# n64cart-v3-soic-16-usbc.net
KiCad netlist of a schematic drawn in EAGLE
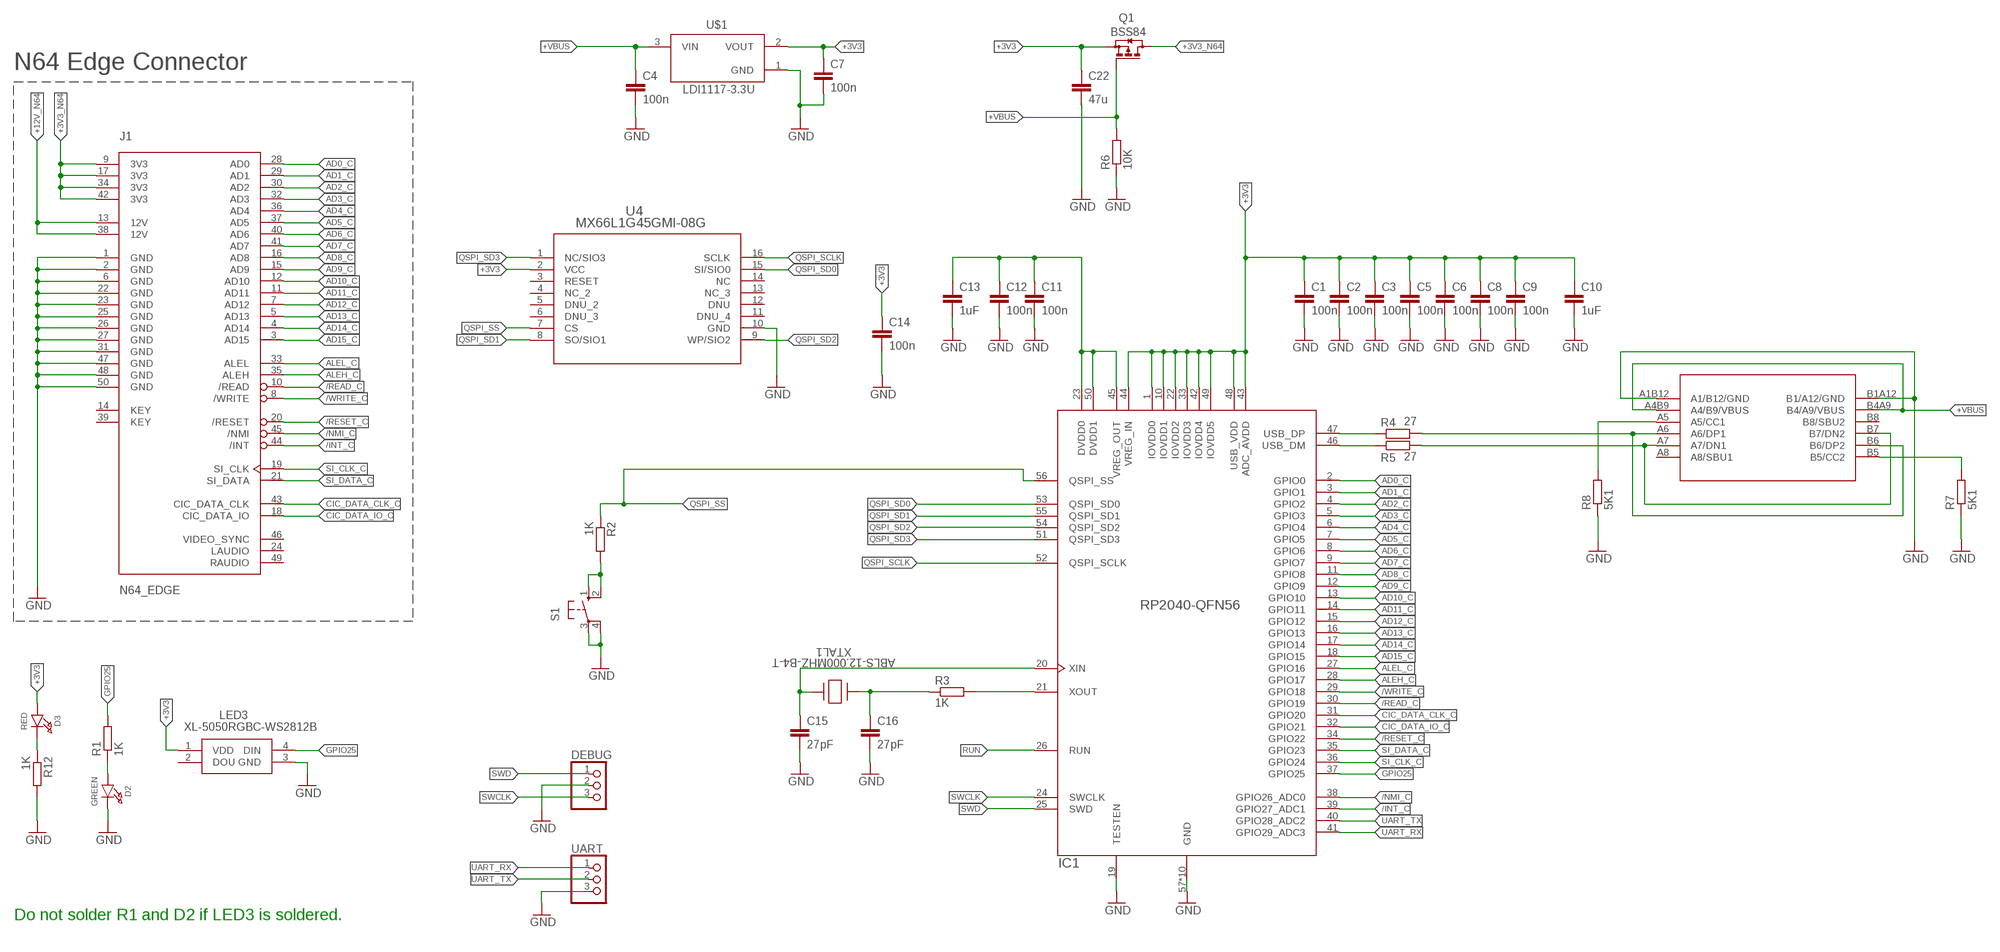
[diagram p0: schematic, sheet 1]

(export (version "E")
  (design (tool "Eeschema 10.0.6"))
  (components
    (comp (ref "C1")
      (value "100n")
      (footprint "eagle-import:C0402")
      (libsource (lib "eagle-import") (part "C-EUC0402"))
    )
    (comp (ref "C2")
      (value "100n")
      (footprint "eagle-import:C0402")
      (libsource (lib "eagle-import") (part "C-EUC0402"))
    )
    (comp (ref "C3")
      (value "100n")
      (footprint "eagle-import:C0402")
      (libsource (lib "eagle-import") (part "C-EUC0402"))
    )
    (comp (ref "C4")
      (value "100n")
      (footprint "eagle-import:C0603")
      (libsource (lib "eagle-import") (part "C-EUC0603"))
    )
    (comp (ref "C5")
      (value "100n")
      (footprint "eagle-import:C0402")
      (libsource (lib "eagle-import") (part "C-EUC0402"))
    )
    (comp (ref "C6")
      (value "100n")
      (footprint "eagle-import:C0402")
      (libsource (lib "eagle-import") (part "C-EUC0402"))
    )
    (comp (ref "C7")
      (value "100n")
      (footprint "eagle-import:C0603")
      (libsource (lib "eagle-import") (part "C-EUC0603"))
    )
    (comp (ref "C8")
      (value "100n")
      (footprint "eagle-import:C0402")
      (libsource (lib "eagle-import") (part "C-EUC0402"))
    )
    (comp (ref "C9")
      (value "100n")
      (footprint "eagle-import:C0402")
      (libsource (lib "eagle-import") (part "C-EUC0402"))
    )
    (comp (ref "C10")
      (value "1uF")
      (footprint "eagle-import:C0402")
      (libsource (lib "eagle-import") (part "C-EUC0402"))
    )
    (comp (ref "C11")
      (value "100n")
      (footprint "eagle-import:C0402")
      (libsource (lib "eagle-import") (part "C-EUC0402"))
    )
    (comp (ref "C12")
      (value "100n")
      (footprint "eagle-import:C0402")
      (libsource (lib "eagle-import") (part "C-EUC0402"))
    )
    (comp (ref "C13")
      (value "1uF")
      (footprint "eagle-import:C0402")
      (libsource (lib "eagle-import") (part "C-EUC0402"))
    )
    (comp (ref "C14")
      (value "100n")
      (footprint "eagle-import:C0402")
      (libsource (lib "eagle-import") (part "C-EUC0402"))
    )
    (comp (ref "C15")
      (value "27pF")
      (footprint "eagle-import:C0402")
      (libsource (lib "eagle-import") (part "C-EUC0402"))
    )
    (comp (ref "C16")
      (value "27pF")
      (footprint "eagle-import:C0402")
      (libsource (lib "eagle-import") (part "C-EUC0402"))
    )
    (comp (ref "C22")
      (value "47u")
      (footprint "eagle-import:C0805")
      (libsource (lib "eagle-import") (part "C-EUC0805"))
    )
    (comp (ref "D2")
      (value "GREEN")
      (footprint "eagle-import:CHIPLED_0603_NOOUTLINE")
      (libsource (lib "eagle-import") (part "LED0603_NOOUTLINE"))
    )
    (comp (ref "D3")
      (value "RED")
      (footprint "eagle-import:CHIPLED_0603_NOOUTLINE")
      (libsource (lib "eagle-import") (part "LED0603_NOOUTLINE"))
    )
    (comp (ref "DEBUG")
      (value "PINHD-1X3")
      (footprint "eagle-import:1X03")
      (libsource (lib "eagle-import") (part "PINHD-1X3"))
    )
    (comp (ref "IC1")
      (value "RP2040-QFN56")
      (footprint "eagle-import:RP2040-QFN-56")
      (libsource (lib "eagle-import") (part "RP2040-QFN56"))
    )
    (comp (ref "J1")
      (value "N64_EDGE")
      (footprint "eagle-import:N64_EDGE")
      (libsource (lib "eagle-import") (part "N64_EDGE"))
    )
    (comp (ref "J2")
      (value "GT-USB-7010")
      (footprint "eagle-import:GT-USB-7010")
      (libsource (lib "eagle-import") (part "GT-USB-7010"))
    )
    (comp (ref "LED3")
      (value "XL-5050RGBC-WS2812B")
      (footprint "eagle-import:XL5050RGBCWS2812B")
      (libsource (lib "eagle-import") (part "XL-5050RGBC-WS2812B"))
    )
    (comp (ref "Q1")
      (value "BSS84")
      (footprint "eagle-import:SOT23")
      (libsource (lib "eagle-import") (part "BSS84"))
    )
    (comp (ref "R1")
      (value "1K")
      (footprint "eagle-import:R0603")
      (libsource (lib "eagle-import") (part "R-EU_R0603"))
    )
    (comp (ref "R2")
      (value "1K")
      (footprint "eagle-import:R0402")
      (libsource (lib "eagle-import") (part "R-EU_R0402"))
    )
    (comp (ref "R3")
      (value "1K")
      (footprint "eagle-import:R0402")
      (libsource (lib "eagle-import") (part "R-EU_R0402"))
    )
    (comp (ref "R4")
      (value "27")
      (footprint "eagle-import:R0402")
      (libsource (lib "eagle-import") (part "R-EU_R0402"))
    )
    (comp (ref "R5")
      (value "27")
      (footprint "eagle-import:R0402")
      (libsource (lib "eagle-import") (part "R-EU_R0402"))
    )
    (comp (ref "R6")
      (value "10K")
      (footprint "eagle-import:R0603")
      (libsource (lib "eagle-import") (part "R-EU_R0603"))
    )
    (comp (ref "R7")
      (value "5K1")
      (footprint "eagle-import:R0603")
      (libsource (lib "eagle-import") (part "R-EU_R0603"))
    )
    (comp (ref "R8")
      (value "5K1")
      (footprint "eagle-import:R0603")
      (libsource (lib "eagle-import") (part "R-EU_R0603"))
    )
    (comp (ref "R12")
      (value "1K")
      (footprint "eagle-import:R0603")
      (libsource (lib "eagle-import") (part "R-EU_R0603"))
    )
    (comp (ref "S1")
      (value "10-XX")
      (footprint "eagle-import:B3F-10XX")
      (fields (field (name "MPN") "B3F-1000"))
      (libsource (lib "eagle-import") (part "10-XX"))
    )
    (comp (ref "U$1")
      (value "LDI1117-3.3U")
      (footprint "eagle-import:LDI1117-3.3U")
      (libsource (lib "eagle-import") (part "LDI1117-3.3U"))
    )
    (comp (ref "U4")
      (value "MX66L1G45GMI-08G")
      (footprint "eagle-import:SOP_16L_300_MAC-L")
      (fields (field (name "COPYRIGHT") "Copyright (C) 2024 Ultra Librarian. All rights reserved."))
      (libsource (lib "eagle-import") (part "MX66L1G45GMI-08GSOP_16L_300_MAC-L"))
    )
    (comp (ref "UART")
      (value "PINHD-1X3")
      (footprint "eagle-import:1X03")
      (libsource (lib "eagle-import") (part "PINHD-1X3"))
    )
    (comp (ref "XTAL1")
      (value "ABLS-12.000MHZ-B4-T")
      (footprint "eagle-import:XTAL_ABLS_ABR")
      (fields (field (name "COPYRIGHT") "Copyright (C) 2022 Ultra Librarian. All rights reserved."))
      (libsource (lib "eagle-import") (part "ABLS-12.000MHZ-B4-T"))
    )
  )
  (nets
    (net (code "1") (name "+3V3") (class "Default")
      (node (ref "C1") (pin "1") (pinfunction "1_1") (pintype "passive"))
      (node (ref "C10") (pin "1") (pinfunction "1_1") (pintype "passive"))
      (node (ref "C14") (pin "1") (pinfunction "1_1") (pintype "passive"))
      (node (ref "C2") (pin "1") (pinfunction "1_1") (pintype "passive"))
      (node (ref "C22") (pin "1") (pinfunction "1_1") (pintype "passive"))
      (node (ref "C3") (pin "1") (pinfunction "1_1") (pintype "passive"))
      (node (ref "C5") (pin "1") (pinfunction "1_1") (pintype "passive"))
      (node (ref "C6") (pin "1") (pinfunction "1_1") (pintype "passive"))
      (node (ref "C7") (pin "1") (pinfunction "1_1") (pintype "passive"))
      (node (ref "C8") (pin "1") (pinfunction "1_1") (pintype "passive"))
      (node (ref "C9") (pin "1") (pinfunction "1_1") (pintype "passive"))
      (node (ref "D3") (pin "A") (pinfunction "A_A") (pintype "passive"))
      (node (ref "IC1") (pin "1") (pinfunction "IOVDD0_1") (pintype "power_in"))
      (node (ref "IC1") (pin "10") (pinfunction "IOVDD1_10") (pintype "power_in"))
      (node (ref "IC1") (pin "22") (pinfunction "IOVDD2_22") (pintype "power_in"))
      (node (ref "IC1") (pin "33") (pinfunction "IOVDD3_33") (pintype "power_in"))
      (node (ref "IC1") (pin "42") (pinfunction "IOVDD4_42") (pintype "power_in"))
      (node (ref "IC1") (pin "43") (pinfunction "ADC_AVDD_43") (pintype "power_in"))
      (node (ref "IC1") (pin "44") (pinfunction "VREG_IN_44") (pintype "power_in"))
      (node (ref "IC1") (pin "48") (pinfunction "USB_VDD_48") (pintype "power_in"))
      (node (ref "IC1") (pin "49") (pinfunction "IOVDD5_49") (pintype "power_in"))
      (node (ref "LED3") (pin "1") (pinfunction "VDD_1") (pintype "bidirectional"))
      (node (ref "Q1") (pin "2") (pinfunction "S_2") (pintype "passive"))
      (node (ref "U$1") (pin "2") (pinfunction "VOUT_2") (pintype "output"))
      (node (ref "U4") (pin "2") (pinfunction "VCC_2") (pintype "power_in"))
    )
    (net (code "2") (name "+3V3_N64") (class "Default")
      (node (ref "J1") (pin "17") (pinfunction "3V3_17") (pintype "power_in"))
      (node (ref "J1") (pin "34") (pinfunction "3V3_34") (pintype "power_in"))
      (node (ref "J1") (pin "42") (pinfunction "3V3_42") (pintype "power_in"))
      (node (ref "J1") (pin "9") (pinfunction "3V3_9") (pintype "power_in"))
      (node (ref "Q1") (pin "3") (pinfunction "D_3") (pintype "passive"))
    )
    (net (code "3") (name "+12V_N64") (class "Default")
      (node (ref "J1") (pin "13") (pinfunction "12V_13") (pintype "power_in"))
      (node (ref "J1") (pin "38") (pinfunction "12V_38") (pintype "power_in"))
    )
    (net (code "4") (name "+VBUS") (class "Default")
      (node (ref "C4") (pin "1") (pinfunction "1_1") (pintype "passive"))
      (node (ref "J2") (pin "A4B9") (pinfunction "A4/B9/VBUS_A4B9") (pintype "bidirectional"))
      (node (ref "J2") (pin "B4A9") (pinfunction "B4/A9/VBUS_B4A9") (pintype "bidirectional"))
      (node (ref "Q1") (pin "1") (pinfunction "G_1") (pintype "passive"))
      (node (ref "R6") (pin "2") (pinfunction "2_2") (pintype "passive"))
      (node (ref "U$1") (pin "3") (pinfunction "VIN_3") (pintype "input"))
    )
    (net (code "5") (name "AD0_C") (class "Default")
      (node (ref "IC1") (pin "2") (pinfunction "GPIO0_2") (pintype "bidirectional"))
      (node (ref "J1") (pin "28") (pinfunction "AD0_28") (pintype "bidirectional"))
    )
    (net (code "6") (name "AD1_C") (class "Default")
      (node (ref "IC1") (pin "3") (pinfunction "GPIO1_3") (pintype "bidirectional"))
      (node (ref "J1") (pin "29") (pinfunction "AD1_29") (pintype "bidirectional"))
    )
    (net (code "7") (name "AD2_C") (class "Default")
      (node (ref "IC1") (pin "4") (pinfunction "GPIO2_4") (pintype "bidirectional"))
      (node (ref "J1") (pin "30") (pinfunction "AD2_30") (pintype "bidirectional"))
    )
    (net (code "8") (name "AD3_C") (class "Default")
      (node (ref "IC1") (pin "5") (pinfunction "GPIO3_5") (pintype "bidirectional"))
      (node (ref "J1") (pin "32") (pinfunction "AD3_32") (pintype "bidirectional"))
    )
    (net (code "9") (name "AD4_C") (class "Default")
      (node (ref "IC1") (pin "6") (pinfunction "GPIO4_6") (pintype "bidirectional"))
      (node (ref "J1") (pin "36") (pinfunction "AD4_36") (pintype "bidirectional"))
    )
    (net (code "10") (name "AD5_C") (class "Default")
      (node (ref "IC1") (pin "7") (pinfunction "GPIO5_7") (pintype "bidirectional"))
      (node (ref "J1") (pin "37") (pinfunction "AD5_37") (pintype "bidirectional"))
    )
    (net (code "11") (name "AD6_C") (class "Default")
      (node (ref "IC1") (pin "8") (pinfunction "GPIO6_8") (pintype "bidirectional"))
      (node (ref "J1") (pin "40") (pinfunction "AD6_40") (pintype "bidirectional"))
    )
    (net (code "12") (name "AD7_C") (class "Default")
      (node (ref "IC1") (pin "9") (pinfunction "GPIO7_9") (pintype "bidirectional"))
      (node (ref "J1") (pin "41") (pinfunction "AD7_41") (pintype "bidirectional"))
    )
    (net (code "13") (name "AD8_C") (class "Default")
      (node (ref "IC1") (pin "11") (pinfunction "GPIO8_11") (pintype "bidirectional"))
      (node (ref "J1") (pin "16") (pinfunction "AD8_16") (pintype "bidirectional"))
    )
    (net (code "14") (name "AD9_C") (class "Default")
      (node (ref "IC1") (pin "12") (pinfunction "GPIO9_12") (pintype "bidirectional"))
      (node (ref "J1") (pin "15") (pinfunction "AD9_15") (pintype "bidirectional"))
    )
    (net (code "15") (name "AD10_C") (class "Default")
      (node (ref "IC1") (pin "13") (pinfunction "GPIO10_13") (pintype "bidirectional"))
      (node (ref "J1") (pin "12") (pinfunction "AD10_12") (pintype "bidirectional"))
    )
    (net (code "16") (name "AD11_C") (class "Default")
      (node (ref "IC1") (pin "14") (pinfunction "GPIO11_14") (pintype "bidirectional"))
      (node (ref "J1") (pin "11") (pinfunction "AD11_11") (pintype "bidirectional"))
    )
    (net (code "17") (name "AD12_C") (class "Default")
      (node (ref "IC1") (pin "15") (pinfunction "GPIO12_15") (pintype "bidirectional"))
      (node (ref "J1") (pin "7") (pinfunction "AD12_7") (pintype "bidirectional"))
    )
    (net (code "18") (name "AD13_C") (class "Default")
      (node (ref "IC1") (pin "16") (pinfunction "GPIO13_16") (pintype "bidirectional"))
      (node (ref "J1") (pin "5") (pinfunction "AD13_5") (pintype "bidirectional"))
    )
    (net (code "19") (name "AD14_C") (class "Default")
      (node (ref "IC1") (pin "17") (pinfunction "GPIO14_17") (pintype "bidirectional"))
      (node (ref "J1") (pin "4") (pinfunction "AD14_4") (pintype "bidirectional"))
    )
    (net (code "20") (name "AD15_C") (class "Default")
      (node (ref "IC1") (pin "18") (pinfunction "GPIO15_18") (pintype "bidirectional"))
      (node (ref "J1") (pin "3") (pinfunction "AD15_3") (pintype "bidirectional"))
    )
    (net (code "21") (name "ALEH_C") (class "Default")
      (node (ref "IC1") (pin "28") (pinfunction "GPIO17_28") (pintype "bidirectional"))
      (node (ref "J1") (pin "35") (pinfunction "ALEH_35") (pintype "output"))
    )
    (net (code "22") (name "ALEL_C") (class "Default")
      (node (ref "IC1") (pin "27") (pinfunction "GPIO16_27") (pintype "bidirectional"))
      (node (ref "J1") (pin "33") (pinfunction "ALEL_33") (pintype "output"))
    )
    (net (code "23") (name "CIC_DATA_CLK_C") (class "Default")
      (node (ref "IC1") (pin "31") (pinfunction "GPIO20_31") (pintype "bidirectional"))
      (node (ref "J1") (pin "43") (pinfunction "CIC_DATA_CLK_43") (pintype "output"))
    )
    (net (code "24") (name "CIC_DATA_IO_C") (class "Default")
      (node (ref "IC1") (pin "32") (pinfunction "GPIO21_32") (pintype "bidirectional"))
      (node (ref "J1") (pin "18") (pinfunction "CIC_DATA_IO_18") (pintype "bidirectional"))
    )
    (net (code "25") (name "GND") (class "Default")
      (node (ref "C1") (pin "2") (pinfunction "2_2") (pintype "passive"))
      (node (ref "C10") (pin "2") (pinfunction "2_2") (pintype "passive"))
      (node (ref "C11") (pin "2") (pinfunction "2_2") (pintype "passive"))
      (node (ref "C12") (pin "2") (pinfunction "2_2") (pintype "passive"))
      (node (ref "C13") (pin "2") (pinfunction "2_2") (pintype "passive"))
      (node (ref "C14") (pin "2") (pinfunction "2_2") (pintype "passive"))
      (node (ref "C15") (pin "2") (pinfunction "2_2") (pintype "passive"))
      (node (ref "C16") (pin "2") (pinfunction "2_2") (pintype "passive"))
      (node (ref "C2") (pin "2") (pinfunction "2_2") (pintype "passive"))
      (node (ref "C22") (pin "2") (pinfunction "2_2") (pintype "passive"))
      (node (ref "C3") (pin "2") (pinfunction "2_2") (pintype "passive"))
      (node (ref "C4") (pin "2") (pinfunction "2_2") (pintype "passive"))
      (node (ref "C5") (pin "2") (pinfunction "2_2") (pintype "passive"))
      (node (ref "C6") (pin "2") (pinfunction "2_2") (pintype "passive"))
      (node (ref "C7") (pin "2") (pinfunction "2_2") (pintype "passive"))
      (node (ref "C8") (pin "2") (pinfunction "2_2") (pintype "passive"))
      (node (ref "C9") (pin "2") (pinfunction "2_2") (pintype "passive"))
      (node (ref "D2") (pin "C") (pinfunction "C_C") (pintype "passive"))
      (node (ref "DEBUG") (pin "2") (pinfunction "2_2") (pintype "passive"))
      (node (ref "IC1") (pin "19") (pinfunction "TESTEN_19") (pintype "passive"))
      (node (ref "IC1") (pin "57") (pinfunction "GND_57") (pintype "power_in"))
      (node (ref "IC1") (pin "58") (pinfunction "GND_58") (pintype "power_in"))
      (node (ref "IC1") (pin "59") (pinfunction "GND_59") (pintype "power_in"))
      (node (ref "IC1") (pin "60") (pinfunction "GND_60") (pintype "power_in"))
      (node (ref "IC1") (pin "61") (pinfunction "GND_61") (pintype "power_in"))
      (node (ref "IC1") (pin "62") (pinfunction "GND_62") (pintype "power_in"))
      (node (ref "IC1") (pin "63") (pinfunction "GND_63") (pintype "power_in"))
      (node (ref "IC1") (pin "64") (pinfunction "GND_64") (pintype "power_in"))
      (node (ref "IC1") (pin "65") (pinfunction "GND_65") (pintype "power_in"))
      (node (ref "IC1") (pin "66") (pinfunction "GND_66") (pintype "power_in"))
      (node (ref "J1") (pin "1") (pinfunction "GND_1") (pintype "power_in"))
      (node (ref "J1") (pin "2") (pinfunction "GND_2") (pintype "power_in"))
      (node (ref "J1") (pin "22") (pinfunction "GND_22") (pintype "power_in"))
      (node (ref "J1") (pin "23") (pinfunction "GND_23") (pintype "power_in"))
      (node (ref "J1") (pin "25") (pinfunction "GND_25") (pintype "power_in"))
      (node (ref "J1") (pin "26") (pinfunction "GND_26") (pintype "power_in"))
      (node (ref "J1") (pin "27") (pinfunction "GND_27") (pintype "power_in"))
      (node (ref "J1") (pin "31") (pinfunction "GND_31") (pintype "power_in"))
      (node (ref "J1") (pin "47") (pinfunction "GND_47") (pintype "power_in"))
      (node (ref "J1") (pin "48") (pinfunction "GND_48") (pintype "power_in"))
      (node (ref "J1") (pin "50") (pinfunction "GND_50") (pintype "power_in"))
      (node (ref "J1") (pin "6") (pinfunction "GND_6") (pintype "power_in"))
      (node (ref "J2") (pin "A1B12") (pinfunction "A1/B12/GND_A1B12") (pintype "bidirectional"))
      (node (ref "J2") (pin "B1A12") (pinfunction "B1/A12/GND_B1A12") (pintype "bidirectional"))
      (node (ref "LED3") (pin "3") (pinfunction "GND_3") (pintype "bidirectional"))
      (node (ref "R12") (pin "2") (pinfunction "2_2") (pintype "passive"))
      (node (ref "R6") (pin "1") (pinfunction "1_1") (pintype "passive"))
      (node (ref "R7") (pin "1") (pinfunction "1_1") (pintype "passive"))
      (node (ref "R8") (pin "1") (pinfunction "1_1") (pintype "passive"))
      (node (ref "S1") (pin "3") (pinfunction "P_3") (pintype "passive"))
      (node (ref "S1") (pin "4") (pinfunction "P1_4") (pintype "passive"))
      (node (ref "U$1") (pin "1") (pinfunction "GND_1") (pintype "power_in"))
      (node (ref "U4") (pin "10") (pinfunction "GND_10") (pintype "passive"))
      (node (ref "UART") (pin "3") (pinfunction "3_3") (pintype "passive"))
    )
    (net (code "26") (name "GPIO25") (class "Default")
      (node (ref "IC1") (pin "37") (pinfunction "GPIO25_37") (pintype "bidirectional"))
      (node (ref "LED3") (pin "4") (pinfunction "DIN_4") (pintype "bidirectional"))
      (node (ref "R1") (pin "2") (pinfunction "2_2") (pintype "passive"))
    )
    (net (code "27") (name "Net-(C16-Pad1)") (class "Default")
      (node (ref "C16") (pin "1") (pinfunction "1_1") (pintype "passive"))
      (node (ref "R3") (pin "1") (pinfunction "1_1") (pintype "passive"))
      (node (ref "XTAL1") (pin "1") (pinfunction "1_1") (pintype "passive"))
    )
    (net (code "28") (name "Net-(D2-PadA)") (class "Default")
      (node (ref "D2") (pin "A") (pinfunction "A_A") (pintype "passive"))
      (node (ref "R1") (pin "1") (pinfunction "1_1") (pintype "passive"))
    )
    (net (code "29") (name "Net-(D3-PadC)") (class "Default")
      (node (ref "D3") (pin "C") (pinfunction "C_C") (pintype "passive"))
      (node (ref "R12") (pin "1") (pinfunction "1_1") (pintype "passive"))
    )
    (net (code "30") (name "Net-(IC1-DVDD0)") (class "Default")
      (node (ref "C11") (pin "1") (pinfunction "1_1") (pintype "passive"))
      (node (ref "C12") (pin "1") (pinfunction "1_1") (pintype "passive"))
      (node (ref "C13") (pin "1") (pinfunction "1_1") (pintype "passive"))
      (node (ref "IC1") (pin "23") (pinfunction "DVDD0_23") (pintype "power_in"))
      (node (ref "IC1") (pin "45") (pinfunction "VREG_OUT_45") (pintype "power_in"))
      (node (ref "IC1") (pin "50") (pinfunction "DVDD1_50") (pintype "power_in"))
    )
    (net (code "31") (name "Net-(IC1-USB_DM)") (class "Default")
      (node (ref "IC1") (pin "46") (pinfunction "USB_DM_46") (pintype "bidirectional"))
      (node (ref "R5") (pin "1") (pinfunction "1_1") (pintype "passive"))
    )
    (net (code "32") (name "Net-(IC1-USB_DP)") (class "Default")
      (node (ref "IC1") (pin "47") (pinfunction "USB_DP_47") (pintype "bidirectional"))
      (node (ref "R4") (pin "1") (pinfunction "1_1") (pintype "passive"))
    )
    (net (code "33") (name "Net-(IC1-XIN)") (class "Default")
      (node (ref "C15") (pin "1") (pinfunction "1_1") (pintype "passive"))
      (node (ref "IC1") (pin "20") (pinfunction "XIN_20") (pintype "input"))
      (node (ref "XTAL1") (pin "2") (pinfunction "2_2") (pintype "passive"))
    )
    (net (code "34") (name "Net-(IC1-XOUT)") (class "Default")
      (node (ref "IC1") (pin "21") (pinfunction "XOUT_21") (pintype "passive"))
      (node (ref "R3") (pin "2") (pinfunction "2_2") (pintype "passive"))
    )
    (net (code "35") (name "Net-(J2-A5{slash}CC1)") (class "Default")
      (node (ref "J2") (pin "A5") (pinfunction "A5/CC1_A5") (pintype "bidirectional"))
      (node (ref "R8") (pin "2") (pinfunction "2_2") (pintype "passive"))
    )
    (net (code "36") (name "Net-(J2-A6{slash}DP1)") (class "Default")
      (node (ref "J2") (pin "A6") (pinfunction "A6/DP1_A6") (pintype "bidirectional"))
      (node (ref "J2") (pin "B6") (pinfunction "B6/DP2_B6") (pintype "bidirectional"))
      (node (ref "R4") (pin "2") (pinfunction "2_2") (pintype "passive"))
    )
    (net (code "37") (name "Net-(J2-A7{slash}DN1)") (class "Default")
      (node (ref "J2") (pin "A7") (pinfunction "A7/DN1_A7") (pintype "bidirectional"))
      (node (ref "J2") (pin "B7") (pinfunction "B7/DN2_B7") (pintype "bidirectional"))
      (node (ref "R5") (pin "2") (pinfunction "2_2") (pintype "passive"))
    )
    (net (code "38") (name "Net-(J2-B5{slash}CC2)") (class "Default")
      (node (ref "J2") (pin "B5") (pinfunction "B5/CC2_B5") (pintype "bidirectional"))
      (node (ref "R7") (pin "2") (pinfunction "2_2") (pintype "passive"))
    )
    (net (code "39") (name "Net-(S1-S)") (class "Default")
      (node (ref "R2") (pin "2") (pinfunction "2_2") (pintype "passive"))
      (node (ref "S1") (pin "1") (pinfunction "S_1") (pintype "passive"))
      (node (ref "S1") (pin "2") (pinfunction "S1_2") (pintype "passive"))
    )
    (net (code "40") (name "QSPI_SCLK") (class "Default")
      (node (ref "IC1") (pin "52") (pinfunction "QSPI_SCLK_52") (pintype "output"))
      (node (ref "U4") (pin "16") (pinfunction "SCLK_16") (pintype "input"))
    )
    (net (code "41") (name "QSPI_SD0") (class "Default")
      (node (ref "IC1") (pin "53") (pinfunction "QSPI_SD0_53") (pintype "bidirectional"))
      (node (ref "U4") (pin "15") (pinfunction "SI/SIO0_15") (pintype "bidirectional"))
    )
    (net (code "42") (name "QSPI_SD1") (class "Default")
      (node (ref "IC1") (pin "55") (pinfunction "QSPI_SD1_55") (pintype "bidirectional"))
      (node (ref "U4") (pin "8") (pinfunction "SO/SIO1_8") (pintype "bidirectional"))
    )
    (net (code "43") (name "QSPI_SD2") (class "Default")
      (node (ref "IC1") (pin "54") (pinfunction "QSPI_SD2_54") (pintype "bidirectional"))
      (node (ref "U4") (pin "9") (pinfunction "WP/SIO2_9") (pintype "bidirectional"))
    )
    (net (code "44") (name "QSPI_SD3") (class "Default")
      (node (ref "IC1") (pin "51") (pinfunction "QSPI_SD3_51") (pintype "bidirectional"))
      (node (ref "U4") (pin "1") (pinfunction "NC/SIO3_1") (pintype "passive"))
    )
    (net (code "45") (name "QSPI_SS") (class "Default")
      (node (ref "IC1") (pin "56") (pinfunction "QSPI_SS_56") (pintype "bidirectional"))
      (node (ref "R2") (pin "1") (pinfunction "1_1") (pintype "passive"))
      (node (ref "U4") (pin "7") (pinfunction "CS_7") (pintype "input"))
    )
    (net (code "46") (name "RUN") (class "Default")
      (node (ref "IC1") (pin "26") (pinfunction "RUN_26") (pintype "input"))
    )
    (net (code "47") (name "SI_CLK_C") (class "Default")
      (node (ref "IC1") (pin "36") (pinfunction "GPIO24_36") (pintype "bidirectional"))
      (node (ref "J1") (pin "19") (pinfunction "SI_CLK_19") (pintype "output"))
    )
    (net (code "48") (name "SI_DATA_C") (class "Default")
      (node (ref "IC1") (pin "35") (pinfunction "GPIO23_35") (pintype "bidirectional"))
      (node (ref "J1") (pin "21") (pinfunction "SI_DATA_21") (pintype "bidirectional"))
    )
    (net (code "49") (name "SWCLK") (class "Default")
      (node (ref "DEBUG") (pin "3") (pinfunction "3_3") (pintype "passive"))
      (node (ref "IC1") (pin "24") (pinfunction "SWCLK_24") (pintype "output"))
    )
    (net (code "50") (name "SWD") (class "Default")
      (node (ref "DEBUG") (pin "1") (pinfunction "1_1") (pintype "passive"))
      (node (ref "IC1") (pin "25") (pinfunction "SWD_25") (pintype "bidirectional"))
    )
    (net (code "51") (name "UART_RX") (class "Default")
      (node (ref "IC1") (pin "41") (pinfunction "GPIO29_ADC3_41") (pintype "bidirectional"))
      (node (ref "UART") (pin "1") (pinfunction "1_1") (pintype "passive"))
    )
    (net (code "52") (name "UART_TX") (class "Default")
      (node (ref "IC1") (pin "40") (pinfunction "GPIO28_ADC2_40") (pintype "bidirectional"))
      (node (ref "UART") (pin "2") (pinfunction "2_2") (pintype "passive"))
    )
    (net (code "53") (name "unconnected-(J1-KEY-Pad14)") (class "Default")
      (node (ref "J1") (pin "14") (pinfunction "KEY_14") (pintype "no_connect"))
    )
    (net (code "54") (name "unconnected-(J1-KEY-Pad39)") (class "Default")
      (node (ref "J1") (pin "39") (pinfunction "KEY_39") (pintype "no_connect"))
    )
    (net (code "55") (name "unconnected-(J1-LAUDIO-Pad24)") (class "Default")
      (node (ref "J1") (pin "24") (pinfunction "LAUDIO_24") (pintype "input"))
    )
    (net (code "56") (name "unconnected-(J1-RAUDIO-Pad49)") (class "Default")
      (node (ref "J1") (pin "49") (pinfunction "RAUDIO_49") (pintype "input"))
    )
    (net (code "57") (name "unconnected-(J1-VIDEO_SYNC-Pad46)") (class "Default")
      (node (ref "J1") (pin "46") (pinfunction "VIDEO_SYNC_46") (pintype "output"))
    )
    (net (code "58") (name "unconnected-(J2-A8{slash}SBU1-PadA8)") (class "Default")
      (node (ref "J2") (pin "A8") (pinfunction "A8/SBU1_A8") (pintype "bidirectional"))
    )
    (net (code "59") (name "unconnected-(J2-B8{slash}SBU2-PadB8)") (class "Default")
      (node (ref "J2") (pin "B8") (pinfunction "B8/SBU2_B8") (pintype "bidirectional"))
    )
    (net (code "60") (name "unconnected-(LED3-DOU-Pad2)") (class "Default")
      (node (ref "LED3") (pin "2") (pinfunction "DOU_2") (pintype "bidirectional"))
    )
    (net (code "61") (name "unconnected-(U4-DNU-Pad12)") (class "Default")
      (node (ref "U4") (pin "12") (pinfunction "DNU_12") (pintype "no_connect"))
    )
    (net (code "62") (name "unconnected-(U4-DNU_2-Pad5)") (class "Default")
      (node (ref "U4") (pin "5") (pinfunction "DNU_2_5") (pintype "no_connect"))
    )
    (net (code "63") (name "unconnected-(U4-DNU_3-Pad6)") (class "Default")
      (node (ref "U4") (pin "6") (pinfunction "DNU_3_6") (pintype "no_connect"))
    )
    (net (code "64") (name "unconnected-(U4-DNU_4-Pad11)") (class "Default")
      (node (ref "U4") (pin "11") (pinfunction "DNU_4_11") (pintype "no_connect"))
    )
    (net (code "65") (name "unconnected-(U4-NC-Pad14)") (class "Default")
      (node (ref "U4") (pin "14") (pinfunction "NC_14") (pintype "no_connect"))
    )
    (net (code "66") (name "unconnected-(U4-NC_2-Pad4)") (class "Default")
      (node (ref "U4") (pin "4") (pinfunction "NC_2_4") (pintype "no_connect"))
    )
    (net (code "67") (name "unconnected-(U4-NC_3-Pad13)") (class "Default")
      (node (ref "U4") (pin "13") (pinfunction "NC_3_13") (pintype "no_connect"))
    )
    (net (code "68") (name "unconnected-(U4-RESET-Pad3)") (class "Default")
      (node (ref "U4") (pin "3") (pinfunction "RESET_3") (pintype "input"))
    )
    (net (code "69") (name "{slash}INT_C") (class "Default")
      (node (ref "IC1") (pin "39") (pinfunction "GPIO27_ADC1_39") (pintype "bidirectional"))
      (node (ref "J1") (pin "44") (pinfunction "/INT_44") (pintype "input"))
    )
    (net (code "70") (name "{slash}NMI_C") (class "Default")
      (node (ref "IC1") (pin "38") (pinfunction "GPIO26_ADC0_38") (pintype "bidirectional"))
      (node (ref "J1") (pin "45") (pinfunction "/NMI_45") (pintype "output"))
    )
    (net (code "71") (name "{slash}READ_C") (class "Default")
      (node (ref "IC1") (pin "30") (pinfunction "GPIO19_30") (pintype "bidirectional"))
      (node (ref "J1") (pin "10") (pinfunction "/READ_10") (pintype "output"))
    )
    (net (code "72") (name "{slash}RESET_C") (class "Default")
      (node (ref "IC1") (pin "34") (pinfunction "GPIO22_34") (pintype "bidirectional"))
      (node (ref "J1") (pin "20") (pinfunction "/RESET_20") (pintype "output"))
    )
    (net (code "73") (name "{slash}WRITE_C") (class "Default")
      (node (ref "IC1") (pin "29") (pinfunction "GPIO18_29") (pintype "bidirectional"))
      (node (ref "J1") (pin "8") (pinfunction "/WRITE_8") (pintype "output"))
    )
  )
)
